# 2puvodni.net
KiCad netlist of a schematic drawn in EAGLE
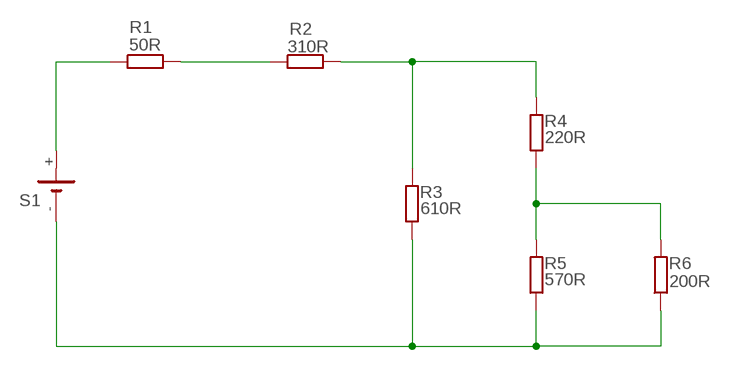
[diagram p0: schematic, sheet 1]

(export (version "E")
  (design (tool "Eeschema 10.0.6"))
  (components
    (comp (ref "R1")
      (value "50R")
      (footprint "eagle-import:0204_7")
      (libsource (lib "eagle-import") (part "R-EU_0204/7"))
    )
    (comp (ref "R2")
      (value "310R")
      (footprint "eagle-import:0204_7")
      (libsource (lib "eagle-import") (part "R-EU_0204/7"))
    )
    (comp (ref "R3")
      (value "610R")
      (footprint "eagle-import:0204_7")
      (libsource (lib "eagle-import") (part "R-EU_0204/7"))
    )
    (comp (ref "R4")
      (value "220R")
      (footprint "eagle-import:0204_7")
      (libsource (lib "eagle-import") (part "R-EU_0204/7"))
    )
    (comp (ref "R5")
      (value "570R")
      (footprint "eagle-import:0204_7")
      (libsource (lib "eagle-import") (part "R-EU_0204/7"))
    )
    (comp (ref "R6")
      (value "200R")
      (footprint "eagle-import:0204_7")
      (libsource (lib "eagle-import") (part "R-EU_0204/7"))
    )
    (comp (ref "S1")
      (value "CH291-1220LF")
      (footprint "eagle-import:CH291-1220LF")
      (libsource (lib "eagle-import") (part "CH291-1220LF"))
    )
  )
  (nets
    (net (code "1") (name "Net-(R1-Pad1)") (class "Default")
      (node (ref "R1") (pin "1") (pinfunction "1_1") (pintype "passive"))
      (node (ref "S1") (pin "+") (pinfunction "+_+") (pintype "passive"))
    )
    (net (code "2") (name "Net-(R1-Pad2)") (class "Default")
      (node (ref "R1") (pin "2") (pinfunction "2_2") (pintype "passive"))
      (node (ref "R2") (pin "1") (pinfunction "1_1") (pintype "passive"))
    )
    (net (code "3") (name "Net-(R2-Pad2)") (class "Default")
      (node (ref "R2") (pin "2") (pinfunction "2_2") (pintype "passive"))
      (node (ref "R3") (pin "2") (pinfunction "2_2") (pintype "passive"))
      (node (ref "R4") (pin "2") (pinfunction "2_2") (pintype "passive"))
    )
    (net (code "4") (name "Net-(R3-Pad1)") (class "Default")
      (node (ref "R3") (pin "1") (pinfunction "1_1") (pintype "passive"))
      (node (ref "R5") (pin "1") (pinfunction "1_1") (pintype "passive"))
      (node (ref "R6") (pin "1") (pinfunction "1_1") (pintype "passive"))
      (node (ref "S1") (pin "-") (pinfunction "-_-") (pintype "passive"))
    )
    (net (code "5") (name "Net-(R4-Pad1)") (class "Default")
      (node (ref "R4") (pin "1") (pinfunction "1_1") (pintype "passive"))
      (node (ref "R5") (pin "2") (pinfunction "2_2") (pintype "passive"))
      (node (ref "R6") (pin "2") (pinfunction "2_2") (pintype "passive"))
    )
  )
)
